# PAPx2-42.net
KiCad netlist of a schematic drawn in EAGLE
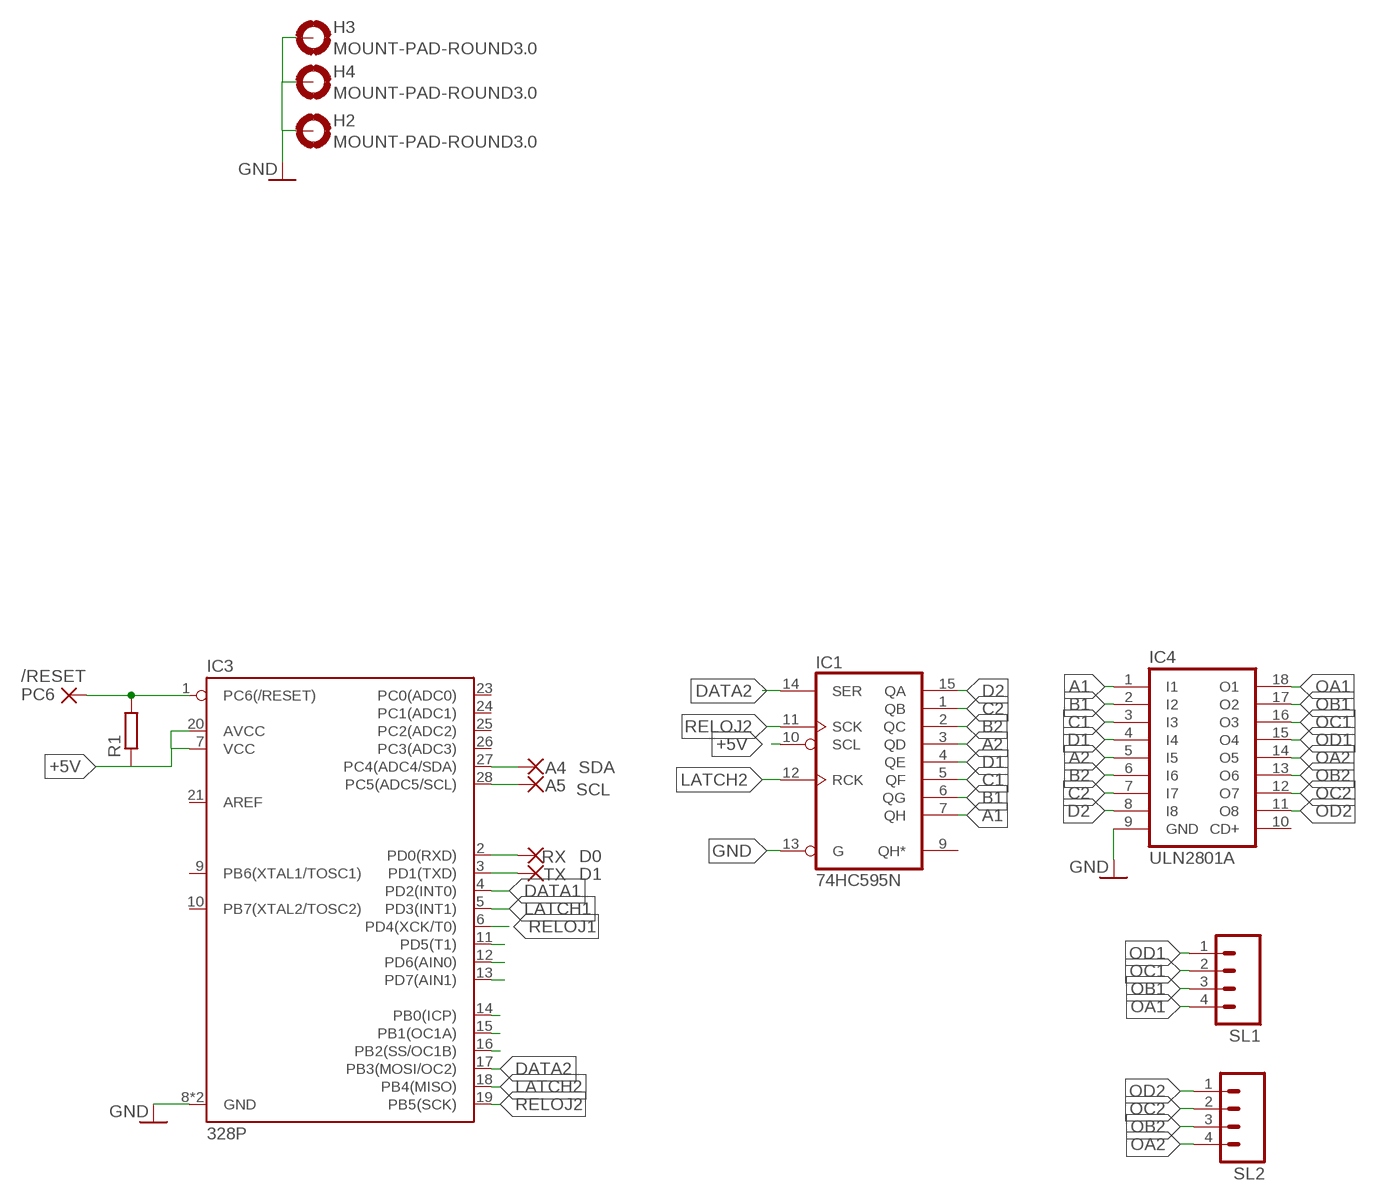
[diagram p0: schematic, sheet 1]

(export (version "E")
  (design (tool "Eeschema 10.0.6"))
  (components
    (comp (ref "/RESET")
      (value "PC6")
      (footprint "eagle-import:1,6_0,8")
      (libsource (lib "eagle-import") (part "WIREPAD1,6/0,8"))
    )
    (comp (ref "A4")
      (value "SDA")
      (footprint "eagle-import:1,6_0,8")
      (libsource (lib "eagle-import") (part "WIREPAD1,6/0,8"))
    )
    (comp (ref "A5")
      (value "SCL")
      (footprint "eagle-import:1,6_0,8")
      (libsource (lib "eagle-import") (part "WIREPAD1,6/0,8"))
    )
    (comp (ref "H2")
      (value "MOUNT-PAD-ROUND3.0")
      (footprint "eagle-import:3,0-PAD")
      (libsource (lib "eagle-import") (part "MOUNT-PAD-ROUND3.0"))
    )
    (comp (ref "H3")
      (value "MOUNT-PAD-ROUND3.0")
      (footprint "eagle-import:3,0-PAD")
      (libsource (lib "eagle-import") (part "MOUNT-PAD-ROUND3.0"))
    )
    (comp (ref "H4")
      (value "MOUNT-PAD-ROUND3.0")
      (footprint "eagle-import:3,0-PAD")
      (libsource (lib "eagle-import") (part "MOUNT-PAD-ROUND3.0"))
    )
    (comp (ref "IC1")
      (value "74HC595N")
      (footprint "eagle-import:DIL16")
      (libsource (lib "eagle-import") (part "74595NHC"))
    )
    (comp (ref "IC3")
      (value "328P")
      (footprint "eagle-import:DIP28")
      (libsource (lib "eagle-import") (part "ATMEGA328P"))
    )
    (comp (ref "IC4")
      (value "ULN2801A")
      (footprint "eagle-import:DIL18")
      (libsource (lib "eagle-import") (part "ULN2801A"))
    )
    (comp (ref "R1")
      (value "R-EU_0204/7")
      (footprint "eagle-import:0204_7")
      (libsource (lib "eagle-import") (part "R-EU_0204/7"))
    )
    (comp (ref "RX")
      (value "D0")
      (footprint "eagle-import:1,6_0,8")
      (libsource (lib "eagle-import") (part "WIREPAD1,6/0,8"))
    )
    (comp (ref "SL1")
      (value "M04")
      (footprint "eagle-import:04P")
      (libsource (lib "eagle-import") (part "M04"))
    )
    (comp (ref "SL2")
      (value "M04")
      (footprint "eagle-import:04P")
      (libsource (lib "eagle-import") (part "M04"))
    )
    (comp (ref "TX")
      (value "D1")
      (footprint "eagle-import:1,6_0,8")
      (libsource (lib "eagle-import") (part "WIREPAD1,6/0,8"))
    )
  )
  (nets
    (net (code "1") (name "+5V") (class "Default")
      (node (ref "IC1") (pin "10") (pinfunction "SCL_10") (pintype "input"))
      (node (ref "IC3") (pin "20") (pinfunction "AVCC_20") (pintype "bidirectional"))
      (node (ref "IC3") (pin "7") (pinfunction "VCC_7") (pintype "bidirectional"))
      (node (ref "R1") (pin "1") (pinfunction "1_1") (pintype "passive"))
    )
    (net (code "2") (name "A1") (class "Default")
      (node (ref "IC1") (pin "7") (pinfunction "QH_7") (pintype "tri_state"))
      (node (ref "IC4") (pin "1") (pinfunction "I1_1") (pintype "input"))
    )
    (net (code "3") (name "A2") (class "Default")
      (node (ref "IC1") (pin "3") (pinfunction "QD_3") (pintype "tri_state"))
      (node (ref "IC4") (pin "5") (pinfunction "I5_5") (pintype "input"))
    )
    (net (code "4") (name "B1") (class "Default")
      (node (ref "IC1") (pin "6") (pinfunction "QG_6") (pintype "tri_state"))
      (node (ref "IC4") (pin "2") (pinfunction "I2_2") (pintype "input"))
    )
    (net (code "5") (name "B2") (class "Default")
      (node (ref "IC1") (pin "2") (pinfunction "QC_2") (pintype "tri_state"))
      (node (ref "IC4") (pin "6") (pinfunction "I6_6") (pintype "input"))
    )
    (net (code "6") (name "C1") (class "Default")
      (node (ref "IC1") (pin "5") (pinfunction "QF_5") (pintype "tri_state"))
      (node (ref "IC4") (pin "3") (pinfunction "I3_3") (pintype "input"))
    )
    (net (code "7") (name "C2") (class "Default")
      (node (ref "IC1") (pin "1") (pinfunction "QB_1") (pintype "tri_state"))
      (node (ref "IC4") (pin "7") (pinfunction "I7_7") (pintype "input"))
    )
    (net (code "8") (name "D1") (class "Default")
      (node (ref "IC1") (pin "4") (pinfunction "QE_4") (pintype "tri_state"))
      (node (ref "IC4") (pin "4") (pinfunction "I4_4") (pintype "input"))
    )
    (net (code "9") (name "D2") (class "Default")
      (node (ref "IC1") (pin "15") (pinfunction "QA_15") (pintype "tri_state"))
      (node (ref "IC4") (pin "8") (pinfunction "I8_8") (pintype "input"))
    )
    (net (code "10") (name "DATA1") (class "Default")
      (node (ref "IC3") (pin "4") (pinfunction "PD2(INT0)_4") (pintype "bidirectional"))
    )
    (net (code "11") (name "DATA2") (class "Default")
      (node (ref "IC1") (pin "14") (pinfunction "SER_14") (pintype "input"))
      (node (ref "IC3") (pin "17") (pinfunction "PB3(MOSI/OC2)_17") (pintype "bidirectional"))
    )
    (net (code "12") (name "GND") (class "Default")
      (node (ref "H2") (pin "B3,0") (pinfunction "MOUNT_B3,0") (pintype "passive"))
      (node (ref "H3") (pin "B3,0") (pinfunction "MOUNT_B3,0") (pintype "passive"))
      (node (ref "H4") (pin "B3,0") (pinfunction "MOUNT_B3,0") (pintype "passive"))
      (node (ref "IC1") (pin "13") (pinfunction "G_13") (pintype "input"))
      (node (ref "IC3") (pin "22") (pinfunction "GND_22") (pintype "bidirectional"))
      (node (ref "IC3") (pin "8") (pinfunction "GND_8") (pintype "bidirectional"))
      (node (ref "IC4") (pin "9") (pinfunction "GND_9") (pintype "power_in"))
    )
    (net (code "13") (name "LATCH1") (class "Default")
      (node (ref "IC3") (pin "5") (pinfunction "PD3(INT1)_5") (pintype "bidirectional"))
    )
    (net (code "14") (name "LATCH2") (class "Default")
      (node (ref "IC1") (pin "12") (pinfunction "RCK_12") (pintype "input"))
      (node (ref "IC3") (pin "18") (pinfunction "PB4(MISO)_18") (pintype "bidirectional"))
    )
    (net (code "15") (name "Net-(/RESET-P)") (class "Default")
      (node (ref "/RESET") (pin "1") (pinfunction "P_1") (pintype "passive"))
      (node (ref "IC3") (pin "1") (pinfunction "PC6(/RESET)_1") (pintype "bidirectional"))
      (node (ref "R1") (pin "2") (pinfunction "2_2") (pintype "passive"))
    )
    (net (code "16") (name "Net-(A4-P)") (class "Default")
      (node (ref "A4") (pin "1") (pinfunction "P_1") (pintype "passive"))
      (node (ref "IC3") (pin "27") (pinfunction "PC4(ADC4/SDA)_27") (pintype "bidirectional"))
    )
    (net (code "17") (name "Net-(A5-P)") (class "Default")
      (node (ref "A5") (pin "1") (pinfunction "P_1") (pintype "passive"))
      (node (ref "IC3") (pin "28") (pinfunction "PC5(ADC5/SCL)_28") (pintype "bidirectional"))
    )
    (net (code "18") (name "Net-(IC3-PD0(RXD))") (class "Default")
      (node (ref "IC3") (pin "2") (pinfunction "PD0(RXD)_2") (pintype "bidirectional"))
      (node (ref "RX") (pin "1") (pinfunction "P_1") (pintype "passive"))
    )
    (net (code "19") (name "Net-(IC3-PD1(TXD))") (class "Default")
      (node (ref "IC3") (pin "3") (pinfunction "PD1(TXD)_3") (pintype "bidirectional"))
      (node (ref "TX") (pin "1") (pinfunction "P_1") (pintype "passive"))
    )
    (net (code "20") (name "OA1") (class "Default")
      (node (ref "IC4") (pin "18") (pinfunction "O1_18") (pintype "open_collector"))
      (node (ref "SL1") (pin "4") (pinfunction "4_4") (pintype "passive"))
    )
    (net (code "21") (name "OA2") (class "Default")
      (node (ref "IC4") (pin "14") (pinfunction "O5_14") (pintype "open_collector"))
      (node (ref "SL2") (pin "4") (pinfunction "4_4") (pintype "passive"))
    )
    (net (code "22") (name "OB1") (class "Default")
      (node (ref "IC4") (pin "17") (pinfunction "O2_17") (pintype "open_collector"))
      (node (ref "SL1") (pin "3") (pinfunction "3_3") (pintype "passive"))
    )
    (net (code "23") (name "OB2") (class "Default")
      (node (ref "IC4") (pin "13") (pinfunction "O6_13") (pintype "open_collector"))
      (node (ref "SL2") (pin "3") (pinfunction "3_3") (pintype "passive"))
    )
    (net (code "24") (name "OC1") (class "Default")
      (node (ref "IC4") (pin "16") (pinfunction "O3_16") (pintype "open_collector"))
      (node (ref "SL1") (pin "2") (pinfunction "2_2") (pintype "passive"))
    )
    (net (code "25") (name "OC2") (class "Default")
      (node (ref "IC4") (pin "12") (pinfunction "O7_12") (pintype "open_collector"))
      (node (ref "SL2") (pin "2") (pinfunction "2_2") (pintype "passive"))
    )
    (net (code "26") (name "OD1") (class "Default")
      (node (ref "IC4") (pin "15") (pinfunction "O4_15") (pintype "open_collector"))
      (node (ref "SL1") (pin "1") (pinfunction "1_1") (pintype "passive"))
    )
    (net (code "27") (name "OD2") (class "Default")
      (node (ref "IC4") (pin "11") (pinfunction "O8_11") (pintype "open_collector"))
      (node (ref "SL2") (pin "1") (pinfunction "1_1") (pintype "passive"))
    )
    (net (code "28") (name "RELOJ1") (class "Default")
      (node (ref "IC3") (pin "6") (pinfunction "PD4(XCK/T0)_6") (pintype "bidirectional"))
    )
    (net (code "29") (name "RELOJ2") (class "Default")
      (node (ref "IC1") (pin "11") (pinfunction "SCK_11") (pintype "input"))
      (node (ref "IC3") (pin "19") (pinfunction "PB5(SCK)_19") (pintype "bidirectional"))
    )
    (net (code "30") (name "unconnected-(IC1A-QH*-Pad9)") (class "Default")
      (node (ref "IC1") (pin "9") (pinfunction "QH*_9") (pintype "tri_state"))
    )
    (net (code "31") (name "unconnected-(IC3-AREF-Pad21)") (class "Default")
      (node (ref "IC3") (pin "21") (pinfunction "AREF_21") (pintype "bidirectional"))
    )
    (net (code "32") (name "unconnected-(IC3-PB0(ICP)-Pad14)") (class "Default")
      (node (ref "IC3") (pin "14") (pinfunction "PB0(ICP)_14") (pintype "bidirectional"))
    )
    (net (code "33") (name "unconnected-(IC3-PB1(OC1A)-Pad15)") (class "Default")
      (node (ref "IC3") (pin "15") (pinfunction "PB1(OC1A)_15") (pintype "bidirectional"))
    )
    (net (code "34") (name "unconnected-(IC3-PB2(SS{slash}OC1B)-Pad16)") (class "Default")
      (node (ref "IC3") (pin "16") (pinfunction "PB2(SS/OC1B)_16") (pintype "bidirectional"))
    )
    (net (code "35") (name "unconnected-(IC3-PB6(XTAL1{slash}TOSC1)-Pad9)") (class "Default")
      (node (ref "IC3") (pin "9") (pinfunction "PB6(XTAL1/TOSC1)_9") (pintype "bidirectional"))
    )
    (net (code "36") (name "unconnected-(IC3-PB7(XTAL2{slash}TOSC2)-Pad10)") (class "Default")
      (node (ref "IC3") (pin "10") (pinfunction "PB7(XTAL2/TOSC2)_10") (pintype "bidirectional"))
    )
    (net (code "37") (name "unconnected-(IC3-PC0(ADC0)-Pad23)") (class "Default")
      (node (ref "IC3") (pin "23") (pinfunction "PC0(ADC0)_23") (pintype "bidirectional"))
    )
    (net (code "38") (name "unconnected-(IC3-PC1(ADC1)-Pad24)") (class "Default")
      (node (ref "IC3") (pin "24") (pinfunction "PC1(ADC1)_24") (pintype "bidirectional"))
    )
    (net (code "39") (name "unconnected-(IC3-PC2(ADC2)-Pad25)") (class "Default")
      (node (ref "IC3") (pin "25") (pinfunction "PC2(ADC2)_25") (pintype "bidirectional"))
    )
    (net (code "40") (name "unconnected-(IC3-PC3(ADC3)-Pad26)") (class "Default")
      (node (ref "IC3") (pin "26") (pinfunction "PC3(ADC3)_26") (pintype "bidirectional"))
    )
    (net (code "41") (name "unconnected-(IC3-PD5(T1)-Pad11)") (class "Default")
      (node (ref "IC3") (pin "11") (pinfunction "PD5(T1)_11") (pintype "bidirectional"))
    )
    (net (code "42") (name "unconnected-(IC3-PD6(AIN0)-Pad12)") (class "Default")
      (node (ref "IC3") (pin "12") (pinfunction "PD6(AIN0)_12") (pintype "bidirectional"))
    )
    (net (code "43") (name "unconnected-(IC3-PD7(AIN1)-Pad13)") (class "Default")
      (node (ref "IC3") (pin "13") (pinfunction "PD7(AIN1)_13") (pintype "bidirectional"))
    )
    (net (code "44") (name "unconnected-(IC4-CD+-Pad10)") (class "Default")
      (node (ref "IC4") (pin "10") (pinfunction "CD+_10") (pintype "passive"))
    )
  )
)
